# PiPico.net
KiCad netlist of a schematic drawn in Altium Designer
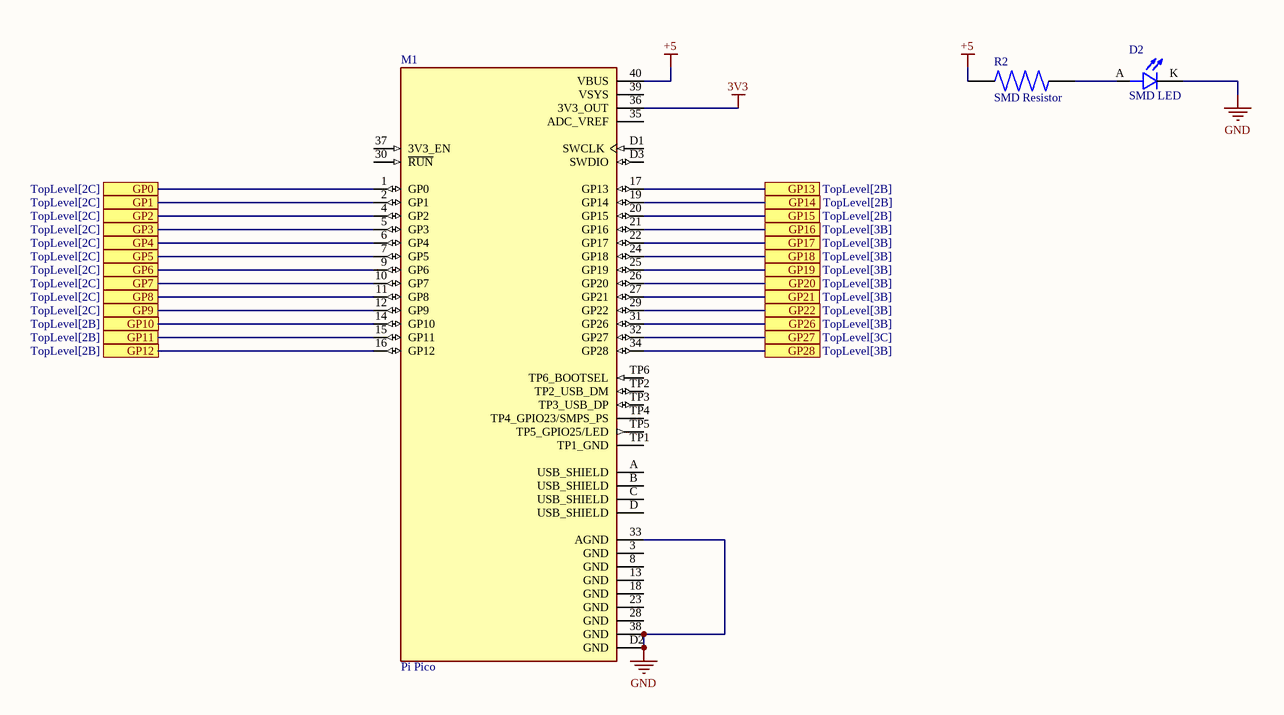
[diagram p0: PiPico.SchDoc]

(export (version "E")
  (design (tool "Eeschema 10.0.6"))
  (components
    (comp (ref "D2")
      (value "SMD LED")
      (footprint "SMD LED-Footprint-1")
      (description "Generic SMD LED")
      (libsource (lib "Tobias") (part "SMD LED-Symbol-1"))
    )
    (comp (ref "M1")
      (value "Pi Pico")
      (footprint "Pi Pico-Footprint-1")
      (libsource (lib "Tobias") (part "Pi Pico-Symbol-1"))
    )
    (comp (ref "R2")
      (value "SMD Resistor")
      (footprint "SMD Resistor-Footprint-1")
      (description "Generic SMD Resistor")
      (libsource (lib "Tobias") (part "SMD Resistor-Symbol-1"))
    )
  )
  (nets
    (net (code "1") (name "+5") (class "Default")
      (node (ref "M1") (pin "40") (pinfunction "VBUS_40") (pintype "power_in"))
      (node (ref "R2") (pin "1") (pinfunction "1_1") (pintype "passive"))
    )
    (net (code "2") (name "/GP0") (class "Default")
      (node (ref "M1") (pin "1") (pinfunction "GP0_1") (pintype "bidirectional"))
    )
    (net (code "3") (name "/GP1") (class "Default")
      (node (ref "M1") (pin "2") (pinfunction "GP1_2") (pintype "bidirectional"))
    )
    (net (code "4") (name "/GP2") (class "Default")
      (node (ref "M1") (pin "4") (pinfunction "GP2_4") (pintype "bidirectional"))
    )
    (net (code "5") (name "/GP3") (class "Default")
      (node (ref "M1") (pin "5") (pinfunction "GP3_5") (pintype "bidirectional"))
    )
    (net (code "6") (name "/GP4") (class "Default")
      (node (ref "M1") (pin "6") (pinfunction "GP4_6") (pintype "bidirectional"))
    )
    (net (code "7") (name "/GP5") (class "Default")
      (node (ref "M1") (pin "7") (pinfunction "GP5_7") (pintype "bidirectional"))
    )
    (net (code "8") (name "/GP6") (class "Default")
      (node (ref "M1") (pin "9") (pinfunction "GP6_9") (pintype "bidirectional"))
    )
    (net (code "9") (name "/GP7") (class "Default")
      (node (ref "M1") (pin "10") (pinfunction "GP7_10") (pintype "bidirectional"))
    )
    (net (code "10") (name "/GP8") (class "Default")
      (node (ref "M1") (pin "11") (pinfunction "GP8_11") (pintype "bidirectional"))
    )
    (net (code "11") (name "/GP9") (class "Default")
      (node (ref "M1") (pin "12") (pinfunction "GP9_12") (pintype "bidirectional"))
    )
    (net (code "12") (name "/GP10") (class "Default")
      (node (ref "M1") (pin "14") (pinfunction "GP10_14") (pintype "bidirectional"))
    )
    (net (code "13") (name "/GP11") (class "Default")
      (node (ref "M1") (pin "15") (pinfunction "GP11_15") (pintype "bidirectional"))
    )
    (net (code "14") (name "/GP12") (class "Default")
      (node (ref "M1") (pin "16") (pinfunction "GP12_16") (pintype "bidirectional"))
    )
    (net (code "15") (name "/GP13") (class "Default")
      (node (ref "M1") (pin "17") (pinfunction "GP13_17") (pintype "bidirectional"))
    )
    (net (code "16") (name "/GP14") (class "Default")
      (node (ref "M1") (pin "19") (pinfunction "GP14_19") (pintype "bidirectional"))
    )
    (net (code "17") (name "/GP15") (class "Default")
      (node (ref "M1") (pin "20") (pinfunction "GP15_20") (pintype "bidirectional"))
    )
    (net (code "18") (name "/GP16") (class "Default")
      (node (ref "M1") (pin "21") (pinfunction "GP16_21") (pintype "bidirectional"))
    )
    (net (code "19") (name "/GP17") (class "Default")
      (node (ref "M1") (pin "22") (pinfunction "GP17_22") (pintype "bidirectional"))
    )
    (net (code "20") (name "/GP18") (class "Default")
      (node (ref "M1") (pin "24") (pinfunction "GP18_24") (pintype "bidirectional"))
    )
    (net (code "21") (name "/GP19") (class "Default")
      (node (ref "M1") (pin "25") (pinfunction "GP19_25") (pintype "bidirectional"))
    )
    (net (code "22") (name "/GP20") (class "Default")
      (node (ref "M1") (pin "26") (pinfunction "GP20_26") (pintype "bidirectional"))
    )
    (net (code "23") (name "/GP21") (class "Default")
      (node (ref "M1") (pin "27") (pinfunction "GP21_27") (pintype "bidirectional"))
    )
    (net (code "24") (name "/GP22") (class "Default")
      (node (ref "M1") (pin "29") (pinfunction "GP22_29") (pintype "bidirectional"))
    )
    (net (code "25") (name "/GP26") (class "Default")
      (node (ref "M1") (pin "31") (pinfunction "GP26_31") (pintype "bidirectional"))
    )
    (net (code "26") (name "/GP27") (class "Default")
      (node (ref "M1") (pin "32") (pinfunction "GP27_32") (pintype "bidirectional"))
    )
    (net (code "27") (name "/GP28") (class "Default")
      (node (ref "M1") (pin "34") (pinfunction "GP28_34") (pintype "bidirectional"))
    )
    (net (code "28") (name "3V3") (class "Default")
      (node (ref "M1") (pin "36") (pinfunction "3V3_OUT_36") (pintype "power_in"))
    )
    (net (code "29") (name "GND") (class "Default")
      (node (ref "D2") (pin "K") (pinfunction "C_K") (pintype "passive"))
      (node (ref "M1") (pin "33") (pinfunction "AGND_33") (pintype "power_in"))
      (node (ref "M1") (pin "38") (pinfunction "GND_38") (pintype "power_in"))
      (node (ref "M1") (pin "D2") (pinfunction "GND_D2") (pintype "power_in"))
    )
    (net (code "30") (name "Net-(D2-PadA)") (class "Default")
      (node (ref "D2") (pin "A") (pinfunction "A_A") (pintype "passive"))
      (node (ref "R2") (pin "2") (pinfunction "2_2") (pintype "passive"))
    )
    (net (code "31") (name "unconnected-(M1-3V3_EN-Pad37)") (class "Default")
      (node (ref "M1") (pin "37") (pinfunction "3V3_EN_37") (pintype "input"))
    )
    (net (code "32") (name "unconnected-(M1-ADC_VREF-Pad35)") (class "Default")
      (node (ref "M1") (pin "35") (pinfunction "ADC_VREF_35") (pintype "power_in"))
    )
    (net (code "33") (name "unconnected-(M1-GND-Pad3)") (class "Default")
      (node (ref "M1") (pin "3") (pinfunction "GND_3") (pintype "power_in"))
    )
    (net (code "34") (name "unconnected-(M1-GND-Pad8)") (class "Default")
      (node (ref "M1") (pin "8") (pinfunction "GND_8") (pintype "power_in"))
    )
    (net (code "35") (name "unconnected-(M1-GND-Pad13)") (class "Default")
      (node (ref "M1") (pin "13") (pinfunction "GND_13") (pintype "power_in"))
    )
    (net (code "36") (name "unconnected-(M1-GND-Pad18)") (class "Default")
      (node (ref "M1") (pin "18") (pinfunction "GND_18") (pintype "power_in"))
    )
    (net (code "37") (name "unconnected-(M1-GND-Pad23)") (class "Default")
      (node (ref "M1") (pin "23") (pinfunction "GND_23") (pintype "power_in"))
    )
    (net (code "38") (name "unconnected-(M1-GND-Pad28)") (class "Default")
      (node (ref "M1") (pin "28") (pinfunction "GND_28") (pintype "power_in"))
    )
    (net (code "39") (name "unconnected-(M1-SWCLK-PadD1)") (class "Default")
      (node (ref "M1") (pin "D1") (pinfunction "SWCLK_D1") (pintype "input"))
    )
    (net (code "40") (name "unconnected-(M1-SWDIO-PadD3)") (class "Default")
      (node (ref "M1") (pin "D3") (pinfunction "SWDIO_D3") (pintype "bidirectional"))
    )
    (net (code "41") (name "unconnected-(M1-TP1_GND-PadTP1)") (class "Default")
      (node (ref "M1") (pin "TP1") (pinfunction "TP1_GND_TP1") (pintype "power_in"))
    )
    (net (code "42") (name "unconnected-(M1-TP2_USB_DM-PadTP2)") (class "Default")
      (node (ref "M1") (pin "TP2") (pinfunction "TP2_USB_DM_TP2") (pintype "bidirectional"))
    )
    (net (code "43") (name "unconnected-(M1-TP3_USB_DP-PadTP3)") (class "Default")
      (node (ref "M1") (pin "TP3") (pinfunction "TP3_USB_DP_TP3") (pintype "bidirectional"))
    )
    (net (code "44") (name "unconnected-(M1-TP4_GPIO23{slash}SMPS_PS-PadTP4)") (class "Default")
      (node (ref "M1") (pin "TP4") (pinfunction "TP4_GPIO23/SMPS_PS_TP4") (pintype "passive"))
    )
    (net (code "45") (name "unconnected-(M1-TP5_GPIO25{slash}LED-PadTP5)") (class "Default")
      (node (ref "M1") (pin "TP5") (pinfunction "TP5_GPIO25/LED_TP5") (pintype "output"))
    )
    (net (code "46") (name "unconnected-(M1-TP6_BOOTSEL-PadTP6)") (class "Default")
      (node (ref "M1") (pin "TP6") (pinfunction "TP6_BOOTSEL_TP6") (pintype "input"))
    )
    (net (code "47") (name "unconnected-(M1-USB_SHIELD-PadA)") (class "Default")
      (node (ref "M1") (pin "A") (pinfunction "USB_SHIELD_A") (pintype "power_in"))
    )
    (net (code "48") (name "unconnected-(M1-USB_SHIELD-PadB)") (class "Default")
      (node (ref "M1") (pin "B") (pinfunction "USB_SHIELD_B") (pintype "power_in"))
    )
    (net (code "49") (name "unconnected-(M1-USB_SHIELD-PadC)") (class "Default")
      (node (ref "M1") (pin "C") (pinfunction "USB_SHIELD_C") (pintype "power_in"))
    )
    (net (code "50") (name "unconnected-(M1-USB_SHIELD-PadD)") (class "Default")
      (node (ref "M1") (pin "D") (pinfunction "USB_SHIELD_D") (pintype "power_in"))
    )
    (net (code "51") (name "unconnected-(M1-VSYS-Pad39)") (class "Default")
      (node (ref "M1") (pin "39") (pinfunction "VSYS_39") (pintype "power_in"))
    )
    (net (code "52") (name "unconnected-(M1-~{RUN}-Pad30)") (class "Default")
      (node (ref "M1") (pin "30") (pinfunction "~{RUN}_30") (pintype "input"))
    )
  )
)
